# buttonsModule.net
KiCad netlist of a schematic drawn in EAGLE
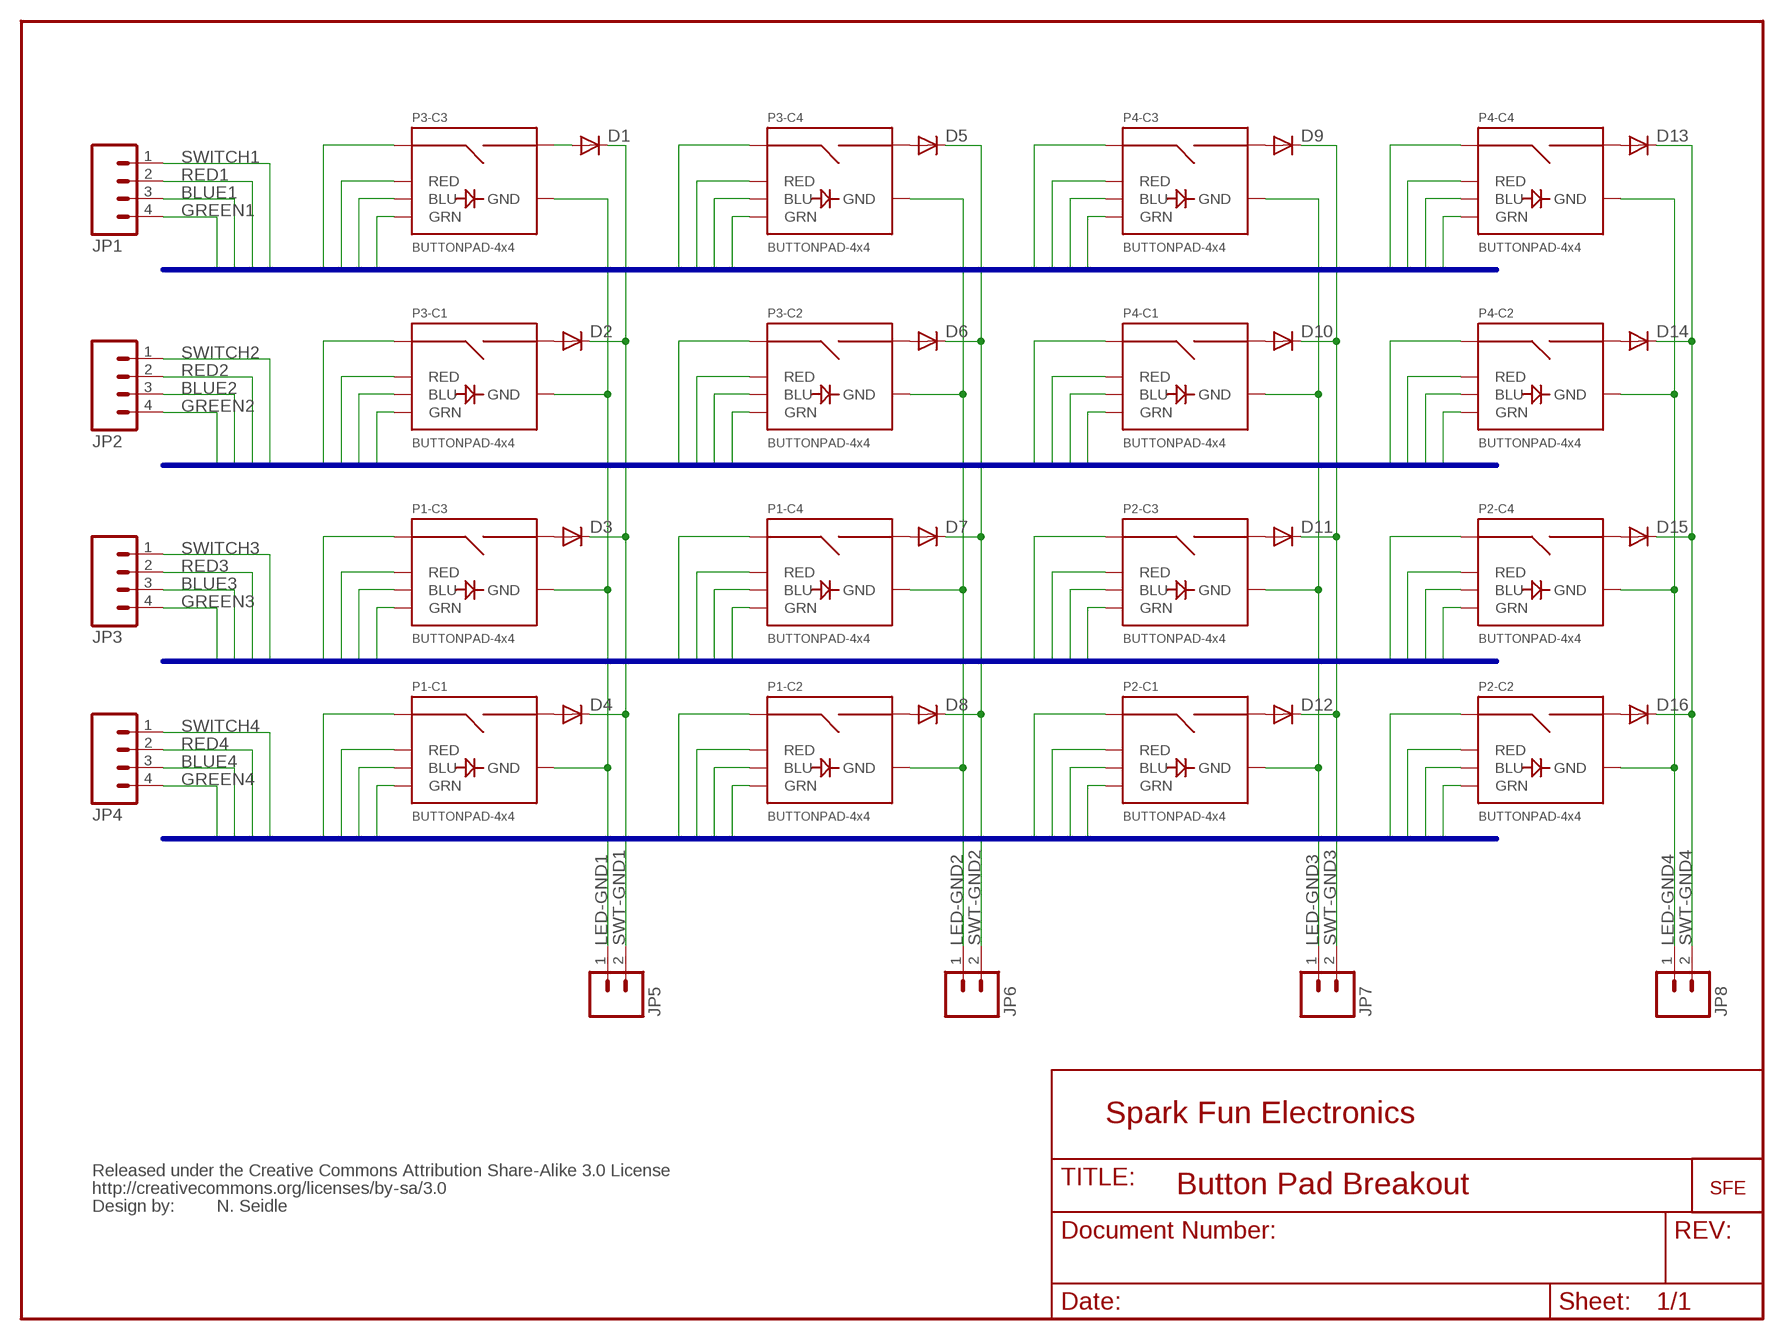
[diagram p0: schematic, sheet 1]

(export (version "E")
  (design (tool "Eeschema 10.0.6"))
  (components
    (comp (ref "D1")
      (value "DIODE-1N4148")
      (footprint "eagle-import:DOIDE-1N4148")
      (libsource (lib "eagle-import") (part "DIODE-1N4148"))
    )
    (comp (ref "D2")
      (value "DIODE-1N4148")
      (footprint "eagle-import:DOIDE-1N4148")
      (libsource (lib "eagle-import") (part "DIODE-1N4148"))
    )
    (comp (ref "D3")
      (value "DIODE-1N4148")
      (footprint "eagle-import:DOIDE-1N4148")
      (libsource (lib "eagle-import") (part "DIODE-1N4148"))
    )
    (comp (ref "D4")
      (value "DIODE-1N4148")
      (footprint "eagle-import:DOIDE-1N4148")
      (libsource (lib "eagle-import") (part "DIODE-1N4148"))
    )
    (comp (ref "D5")
      (value "DIODE-1N4148")
      (footprint "eagle-import:DOIDE-1N4148")
      (libsource (lib "eagle-import") (part "DIODE-1N4148"))
    )
    (comp (ref "D6")
      (value "DIODE-1N4148")
      (footprint "eagle-import:DOIDE-1N4148")
      (libsource (lib "eagle-import") (part "DIODE-1N4148"))
    )
    (comp (ref "D7")
      (value "DIODE-1N4148")
      (footprint "eagle-import:DOIDE-1N4148")
      (libsource (lib "eagle-import") (part "DIODE-1N4148"))
    )
    (comp (ref "D8")
      (value "DIODE-1N4148")
      (footprint "eagle-import:DOIDE-1N4148")
      (libsource (lib "eagle-import") (part "DIODE-1N4148"))
    )
    (comp (ref "D9")
      (value "DIODE-1N4148")
      (footprint "eagle-import:DOIDE-1N4148")
      (libsource (lib "eagle-import") (part "DIODE-1N4148"))
    )
    (comp (ref "D10")
      (value "DIODE-1N4148")
      (footprint "eagle-import:DOIDE-1N4148")
      (libsource (lib "eagle-import") (part "DIODE-1N4148"))
    )
    (comp (ref "D11")
      (value "DIODE-1N4148")
      (footprint "eagle-import:DOIDE-1N4148")
      (libsource (lib "eagle-import") (part "DIODE-1N4148"))
    )
    (comp (ref "D12")
      (value "DIODE-1N4148")
      (footprint "eagle-import:DOIDE-1N4148")
      (libsource (lib "eagle-import") (part "DIODE-1N4148"))
    )
    (comp (ref "D13")
      (value "DIODE-1N4148")
      (footprint "eagle-import:DOIDE-1N4148")
      (libsource (lib "eagle-import") (part "DIODE-1N4148"))
    )
    (comp (ref "D14")
      (value "DIODE-1N4148")
      (footprint "eagle-import:DOIDE-1N4148")
      (libsource (lib "eagle-import") (part "DIODE-1N4148"))
    )
    (comp (ref "D15")
      (value "DIODE-1N4148")
      (footprint "eagle-import:DOIDE-1N4148")
      (libsource (lib "eagle-import") (part "DIODE-1N4148"))
    )
    (comp (ref "D16")
      (value "DIODE-1N4148")
      (footprint "eagle-import:DOIDE-1N4148")
      (libsource (lib "eagle-import") (part "DIODE-1N4148"))
    )
    (comp (ref "JP1")
      (value "M04POLAR")
      (footprint "eagle-import:MOLEX-1X4")
      (libsource (lib "eagle-import") (part "M04POLAR"))
    )
    (comp (ref "JP2")
      (value "M04POLAR")
      (footprint "eagle-import:MOLEX-1X4")
      (libsource (lib "eagle-import") (part "M04POLAR"))
    )
    (comp (ref "JP3")
      (value "M04POLAR")
      (footprint "eagle-import:MOLEX-1X4")
      (libsource (lib "eagle-import") (part "M04POLAR"))
    )
    (comp (ref "JP4")
      (value "M04POLAR")
      (footprint "eagle-import:MOLEX-1X4")
      (libsource (lib "eagle-import") (part "M04POLAR"))
    )
    (comp (ref "JP5")
      (value "M02POLAR")
      (footprint "eagle-import:MOLEX-1X2")
      (libsource (lib "eagle-import") (part "M02POLAR"))
    )
    (comp (ref "JP6")
      (value "M02POLAR")
      (footprint "eagle-import:MOLEX-1X2")
      (libsource (lib "eagle-import") (part "M02POLAR"))
    )
    (comp (ref "JP7")
      (value "M02POLAR")
      (footprint "eagle-import:MOLEX-1X2")
      (libsource (lib "eagle-import") (part "M02POLAR"))
    )
    (comp (ref "JP8")
      (value "M02POLAR")
      (footprint "eagle-import:MOLEX-1X2")
      (libsource (lib "eagle-import") (part "M02POLAR"))
    )
    (comp (ref "P1")
      (value "BUTTONPAD-4x4")
      (footprint "eagle-import:BUTTONPAD-2X2")
      (libsource (lib "eagle-import") (part "BUTTONPAD-2X2"))
    )
    (comp (ref "P2")
      (value "BUTTONPAD-4x4")
      (footprint "eagle-import:BUTTONPAD-2X2")
      (libsource (lib "eagle-import") (part "BUTTONPAD-2X2"))
    )
    (comp (ref "P3")
      (value "BUTTONPAD-4x4")
      (footprint "eagle-import:BUTTONPAD-2X2")
      (libsource (lib "eagle-import") (part "BUTTONPAD-2X2"))
    )
    (comp (ref "P4")
      (value "BUTTONPAD-4x4")
      (footprint "eagle-import:BUTTONPAD-2X2")
      (libsource (lib "eagle-import") (part "BUTTONPAD-2X2"))
    )
    (comp (ref "U$1")
      (value "LOGO-SFE")
      (footprint "eagle-import:SFE-NEW-WEBLOGO")
      (libsource (lib "eagle-import") (part "LOGO-SFE"))
    )
    (comp (ref "U$2")
      (value "CREATIVE_COMMONS")
      (footprint "eagle-import:CREATIVE_COMMONS")
      (libsource (lib "eagle-import") (part "CREATIVE_COMMONS"))
    )
  )
  (nets
    (net (code "1") (name "/BLUE1") (class "Default")
      (node (ref "JP1") (pin "3") (pinfunction "3_3") (pintype "passive"))
      (node (ref "P3") (pin "BLU3") (pinfunction "BLU_BLU3") (pintype "bidirectional"))
      (node (ref "P3") (pin "BLU4") (pinfunction "BLU_BLU4") (pintype "bidirectional"))
      (node (ref "P4") (pin "BLU3") (pinfunction "BLU_BLU3") (pintype "bidirectional"))
      (node (ref "P4") (pin "BLU4") (pinfunction "BLU_BLU4") (pintype "bidirectional"))
    )
    (net (code "2") (name "/BLUE2") (class "Default")
      (node (ref "JP2") (pin "3") (pinfunction "3_3") (pintype "passive"))
      (node (ref "P3") (pin "BLU1") (pinfunction "BLU_BLU1") (pintype "bidirectional"))
      (node (ref "P3") (pin "BLU2") (pinfunction "BLU_BLU2") (pintype "bidirectional"))
      (node (ref "P4") (pin "BLU1") (pinfunction "BLU_BLU1") (pintype "bidirectional"))
      (node (ref "P4") (pin "BLU2") (pinfunction "BLU_BLU2") (pintype "bidirectional"))
    )
    (net (code "3") (name "/BLUE3") (class "Default")
      (node (ref "JP3") (pin "3") (pinfunction "3_3") (pintype "passive"))
      (node (ref "P1") (pin "BLU3") (pinfunction "BLU_BLU3") (pintype "bidirectional"))
      (node (ref "P1") (pin "BLU4") (pinfunction "BLU_BLU4") (pintype "bidirectional"))
      (node (ref "P2") (pin "BLU3") (pinfunction "BLU_BLU3") (pintype "bidirectional"))
      (node (ref "P2") (pin "BLU4") (pinfunction "BLU_BLU4") (pintype "bidirectional"))
    )
    (net (code "4") (name "/BLUE4") (class "Default")
      (node (ref "JP4") (pin "3") (pinfunction "3_3") (pintype "passive"))
      (node (ref "P1") (pin "BLU1") (pinfunction "BLU_BLU1") (pintype "bidirectional"))
      (node (ref "P1") (pin "BLU2") (pinfunction "BLU_BLU2") (pintype "bidirectional"))
      (node (ref "P2") (pin "BLU1") (pinfunction "BLU_BLU1") (pintype "bidirectional"))
      (node (ref "P2") (pin "BLU2") (pinfunction "BLU_BLU2") (pintype "bidirectional"))
    )
    (net (code "5") (name "/GREEN1") (class "Default")
      (node (ref "JP1") (pin "4") (pinfunction "4_4") (pintype "passive"))
      (node (ref "P3") (pin "GRN3") (pinfunction "GRN_GRN3") (pintype "bidirectional"))
      (node (ref "P3") (pin "GRN4") (pinfunction "GRN_GRN4") (pintype "bidirectional"))
      (node (ref "P4") (pin "GRN3") (pinfunction "GRN_GRN3") (pintype "bidirectional"))
      (node (ref "P4") (pin "GRN4") (pinfunction "GRN_GRN4") (pintype "bidirectional"))
    )
    (net (code "6") (name "/GREEN2") (class "Default")
      (node (ref "JP2") (pin "4") (pinfunction "4_4") (pintype "passive"))
      (node (ref "P3") (pin "GRN1") (pinfunction "GRN_GRN1") (pintype "bidirectional"))
      (node (ref "P3") (pin "GRN2") (pinfunction "GRN_GRN2") (pintype "bidirectional"))
      (node (ref "P4") (pin "GRN1") (pinfunction "GRN_GRN1") (pintype "bidirectional"))
      (node (ref "P4") (pin "GRN2") (pinfunction "GRN_GRN2") (pintype "bidirectional"))
    )
    (net (code "7") (name "/GREEN3") (class "Default")
      (node (ref "JP3") (pin "4") (pinfunction "4_4") (pintype "passive"))
      (node (ref "P1") (pin "GRN3") (pinfunction "GRN_GRN3") (pintype "bidirectional"))
      (node (ref "P1") (pin "GRN4") (pinfunction "GRN_GRN4") (pintype "bidirectional"))
      (node (ref "P2") (pin "GRN3") (pinfunction "GRN_GRN3") (pintype "bidirectional"))
      (node (ref "P2") (pin "GRN4") (pinfunction "GRN_GRN4") (pintype "bidirectional"))
    )
    (net (code "8") (name "/GREEN4") (class "Default")
      (node (ref "JP4") (pin "4") (pinfunction "4_4") (pintype "passive"))
      (node (ref "P1") (pin "GRN1") (pinfunction "GRN_GRN1") (pintype "bidirectional"))
      (node (ref "P1") (pin "GRN2") (pinfunction "GRN_GRN2") (pintype "bidirectional"))
      (node (ref "P2") (pin "GRN1") (pinfunction "GRN_GRN1") (pintype "bidirectional"))
      (node (ref "P2") (pin "GRN2") (pinfunction "GRN_GRN2") (pintype "bidirectional"))
    )
    (net (code "9") (name "/LED-GND1") (class "Default")
      (node (ref "JP5") (pin "1") (pinfunction "1_1") (pintype "passive"))
      (node (ref "P1") (pin "GND1") (pinfunction "GND_GND1") (pintype "bidirectional"))
      (node (ref "P1") (pin "GND3") (pinfunction "GND_GND3") (pintype "bidirectional"))
      (node (ref "P3") (pin "GND1") (pinfunction "GND_GND1") (pintype "bidirectional"))
      (node (ref "P3") (pin "GND3") (pinfunction "GND_GND3") (pintype "bidirectional"))
    )
    (net (code "10") (name "/LED-GND2") (class "Default")
      (node (ref "JP6") (pin "1") (pinfunction "1_1") (pintype "passive"))
      (node (ref "P1") (pin "GND2") (pinfunction "GND_GND2") (pintype "bidirectional"))
      (node (ref "P1") (pin "GND4") (pinfunction "GND_GND4") (pintype "bidirectional"))
      (node (ref "P3") (pin "GND2") (pinfunction "GND_GND2") (pintype "bidirectional"))
      (node (ref "P3") (pin "GND4") (pinfunction "GND_GND4") (pintype "bidirectional"))
    )
    (net (code "11") (name "/LED-GND3") (class "Default")
      (node (ref "JP7") (pin "1") (pinfunction "1_1") (pintype "passive"))
      (node (ref "P2") (pin "GND1") (pinfunction "GND_GND1") (pintype "bidirectional"))
      (node (ref "P2") (pin "GND3") (pinfunction "GND_GND3") (pintype "bidirectional"))
      (node (ref "P4") (pin "GND1") (pinfunction "GND_GND1") (pintype "bidirectional"))
      (node (ref "P4") (pin "GND3") (pinfunction "GND_GND3") (pintype "bidirectional"))
    )
    (net (code "12") (name "/LED-GND4") (class "Default")
      (node (ref "JP8") (pin "1") (pinfunction "1_1") (pintype "passive"))
      (node (ref "P2") (pin "GND2") (pinfunction "GND_GND2") (pintype "bidirectional"))
      (node (ref "P2") (pin "GND4") (pinfunction "GND_GND4") (pintype "bidirectional"))
      (node (ref "P4") (pin "GND2") (pinfunction "GND_GND2") (pintype "bidirectional"))
      (node (ref "P4") (pin "GND4") (pinfunction "GND_GND4") (pintype "bidirectional"))
    )
    (net (code "13") (name "/RED1") (class "Default")
      (node (ref "JP1") (pin "2") (pinfunction "2_2") (pintype "passive"))
      (node (ref "P3") (pin "RED3") (pinfunction "RED_RED3") (pintype "bidirectional"))
      (node (ref "P3") (pin "RED4") (pinfunction "RED_RED4") (pintype "bidirectional"))
      (node (ref "P4") (pin "RED3") (pinfunction "RED_RED3") (pintype "bidirectional"))
      (node (ref "P4") (pin "RED4") (pinfunction "RED_RED4") (pintype "bidirectional"))
    )
    (net (code "14") (name "/RED2") (class "Default")
      (node (ref "JP2") (pin "2") (pinfunction "2_2") (pintype "passive"))
      (node (ref "P3") (pin "RED1") (pinfunction "RED_RED1") (pintype "bidirectional"))
      (node (ref "P3") (pin "RED2") (pinfunction "RED_RED2") (pintype "bidirectional"))
      (node (ref "P4") (pin "RED1") (pinfunction "RED_RED1") (pintype "bidirectional"))
      (node (ref "P4") (pin "RED2") (pinfunction "RED_RED2") (pintype "bidirectional"))
    )
    (net (code "15") (name "/RED3") (class "Default")
      (node (ref "JP3") (pin "2") (pinfunction "2_2") (pintype "passive"))
      (node (ref "P1") (pin "RED3") (pinfunction "RED_RED3") (pintype "bidirectional"))
      (node (ref "P1") (pin "RED4") (pinfunction "RED_RED4") (pintype "bidirectional"))
      (node (ref "P2") (pin "RED3") (pinfunction "RED_RED3") (pintype "bidirectional"))
      (node (ref "P2") (pin "RED4") (pinfunction "RED_RED4") (pintype "bidirectional"))
    )
    (net (code "16") (name "/RED4") (class "Default")
      (node (ref "JP4") (pin "2") (pinfunction "2_2") (pintype "passive"))
      (node (ref "P1") (pin "RED1") (pinfunction "RED_RED1") (pintype "bidirectional"))
      (node (ref "P1") (pin "RED2") (pinfunction "RED_RED2") (pintype "bidirectional"))
      (node (ref "P2") (pin "RED1") (pinfunction "RED_RED1") (pintype "bidirectional"))
      (node (ref "P2") (pin "RED2") (pinfunction "RED_RED2") (pintype "bidirectional"))
    )
    (net (code "17") (name "/SWITCH1") (class "Default")
      (node (ref "JP1") (pin "1") (pinfunction "1_1") (pintype "passive"))
      (node (ref "P3") (pin "SIG5") (pinfunction "SIG1_SIG5") (pintype "bidirectional"))
      (node (ref "P3") (pin "SIG7") (pinfunction "SIG1_SIG7") (pintype "bidirectional"))
      (node (ref "P4") (pin "SIG5") (pinfunction "SIG1_SIG5") (pintype "bidirectional"))
      (node (ref "P4") (pin "SIG7") (pinfunction "SIG1_SIG7") (pintype "bidirectional"))
    )
    (net (code "18") (name "/SWITCH2") (class "Default")
      (node (ref "JP2") (pin "1") (pinfunction "1_1") (pintype "passive"))
      (node (ref "P3") (pin "SIG1") (pinfunction "SIG1_SIG1") (pintype "bidirectional"))
      (node (ref "P3") (pin "SIG3") (pinfunction "SIG1_SIG3") (pintype "bidirectional"))
      (node (ref "P4") (pin "SIG1") (pinfunction "SIG1_SIG1") (pintype "bidirectional"))
      (node (ref "P4") (pin "SIG3") (pinfunction "SIG1_SIG3") (pintype "bidirectional"))
    )
    (net (code "19") (name "/SWITCH3") (class "Default")
      (node (ref "JP3") (pin "1") (pinfunction "1_1") (pintype "passive"))
      (node (ref "P1") (pin "SIG5") (pinfunction "SIG1_SIG5") (pintype "bidirectional"))
      (node (ref "P1") (pin "SIG7") (pinfunction "SIG1_SIG7") (pintype "bidirectional"))
      (node (ref "P2") (pin "SIG5") (pinfunction "SIG1_SIG5") (pintype "bidirectional"))
      (node (ref "P2") (pin "SIG7") (pinfunction "SIG1_SIG7") (pintype "bidirectional"))
    )
    (net (code "20") (name "/SWITCH4") (class "Default")
      (node (ref "JP4") (pin "1") (pinfunction "1_1") (pintype "passive"))
      (node (ref "P1") (pin "SIG1") (pinfunction "SIG1_SIG1") (pintype "bidirectional"))
      (node (ref "P1") (pin "SIG3") (pinfunction "SIG1_SIG3") (pintype "bidirectional"))
      (node (ref "P2") (pin "SIG1") (pinfunction "SIG1_SIG1") (pintype "bidirectional"))
      (node (ref "P2") (pin "SIG3") (pinfunction "SIG1_SIG3") (pintype "bidirectional"))
    )
    (net (code "21") (name "/SWT-GND1") (class "Default")
      (node (ref "D1") (pin "P$2") (pinfunction "C_P$2") (pintype "passive"))
      (node (ref "D2") (pin "P$2") (pinfunction "C_P$2") (pintype "passive"))
      (node (ref "D3") (pin "P$2") (pinfunction "C_P$2") (pintype "passive"))
      (node (ref "D4") (pin "P$2") (pinfunction "C_P$2") (pintype "passive"))
      (node (ref "JP5") (pin "2") (pinfunction "2_2") (pintype "passive"))
    )
    (net (code "22") (name "/SWT-GND2") (class "Default")
      (node (ref "D5") (pin "P$2") (pinfunction "C_P$2") (pintype "passive"))
      (node (ref "D6") (pin "P$2") (pinfunction "C_P$2") (pintype "passive"))
      (node (ref "D7") (pin "P$2") (pinfunction "C_P$2") (pintype "passive"))
      (node (ref "D8") (pin "P$2") (pinfunction "C_P$2") (pintype "passive"))
      (node (ref "JP6") (pin "2") (pinfunction "2_2") (pintype "passive"))
    )
    (net (code "23") (name "/SWT-GND3") (class "Default")
      (node (ref "D10") (pin "P$2") (pinfunction "C_P$2") (pintype "passive"))
      (node (ref "D11") (pin "P$2") (pinfunction "C_P$2") (pintype "passive"))
      (node (ref "D12") (pin "P$2") (pinfunction "C_P$2") (pintype "passive"))
      (node (ref "D9") (pin "P$2") (pinfunction "C_P$2") (pintype "passive"))
      (node (ref "JP7") (pin "2") (pinfunction "2_2") (pintype "passive"))
    )
    (net (code "24") (name "/SWT-GND4") (class "Default")
      (node (ref "D13") (pin "P$2") (pinfunction "C_P$2") (pintype "passive"))
      (node (ref "D14") (pin "P$2") (pinfunction "C_P$2") (pintype "passive"))
      (node (ref "D15") (pin "P$2") (pinfunction "C_P$2") (pintype "passive"))
      (node (ref "D16") (pin "P$2") (pinfunction "C_P$2") (pintype "passive"))
      (node (ref "JP8") (pin "2") (pinfunction "2_2") (pintype "passive"))
    )
    (net (code "25") (name "Net-(D1-A)") (class "Default")
      (node (ref "D1") (pin "P$1") (pinfunction "A_P$1") (pintype "passive"))
      (node (ref "P3") (pin "SIG6") (pinfunction "SIG2_SIG6") (pintype "bidirectional"))
    )
    (net (code "26") (name "Net-(D2-A)") (class "Default")
      (node (ref "D2") (pin "P$1") (pinfunction "A_P$1") (pintype "passive"))
      (node (ref "P3") (pin "SIG2") (pinfunction "SIG2_SIG2") (pintype "bidirectional"))
    )
    (net (code "27") (name "Net-(D3-A)") (class "Default")
      (node (ref "D3") (pin "P$1") (pinfunction "A_P$1") (pintype "passive"))
      (node (ref "P1") (pin "SIG6") (pinfunction "SIG2_SIG6") (pintype "bidirectional"))
    )
    (net (code "28") (name "Net-(D4-A)") (class "Default")
      (node (ref "D4") (pin "P$1") (pinfunction "A_P$1") (pintype "passive"))
      (node (ref "P1") (pin "SIG2") (pinfunction "SIG2_SIG2") (pintype "bidirectional"))
    )
    (net (code "29") (name "Net-(D5-A)") (class "Default")
      (node (ref "D5") (pin "P$1") (pinfunction "A_P$1") (pintype "passive"))
      (node (ref "P3") (pin "SIG8") (pinfunction "SIG2_SIG8") (pintype "bidirectional"))
    )
    (net (code "30") (name "Net-(D6-A)") (class "Default")
      (node (ref "D6") (pin "P$1") (pinfunction "A_P$1") (pintype "passive"))
      (node (ref "P3") (pin "SIG4") (pinfunction "SIG2_SIG4") (pintype "bidirectional"))
    )
    (net (code "31") (name "Net-(D7-A)") (class "Default")
      (node (ref "D7") (pin "P$1") (pinfunction "A_P$1") (pintype "passive"))
      (node (ref "P1") (pin "SIG8") (pinfunction "SIG2_SIG8") (pintype "bidirectional"))
    )
    (net (code "32") (name "Net-(D8-A)") (class "Default")
      (node (ref "D8") (pin "P$1") (pinfunction "A_P$1") (pintype "passive"))
      (node (ref "P1") (pin "SIG4") (pinfunction "SIG2_SIG4") (pintype "bidirectional"))
    )
    (net (code "33") (name "Net-(D9-A)") (class "Default")
      (node (ref "D9") (pin "P$1") (pinfunction "A_P$1") (pintype "passive"))
      (node (ref "P4") (pin "SIG6") (pinfunction "SIG2_SIG6") (pintype "bidirectional"))
    )
    (net (code "34") (name "Net-(D10-A)") (class "Default")
      (node (ref "D10") (pin "P$1") (pinfunction "A_P$1") (pintype "passive"))
      (node (ref "P4") (pin "SIG2") (pinfunction "SIG2_SIG2") (pintype "bidirectional"))
    )
    (net (code "35") (name "Net-(D11-A)") (class "Default")
      (node (ref "D11") (pin "P$1") (pinfunction "A_P$1") (pintype "passive"))
      (node (ref "P2") (pin "SIG6") (pinfunction "SIG2_SIG6") (pintype "bidirectional"))
    )
    (net (code "36") (name "Net-(D12-A)") (class "Default")
      (node (ref "D12") (pin "P$1") (pinfunction "A_P$1") (pintype "passive"))
      (node (ref "P2") (pin "SIG2") (pinfunction "SIG2_SIG2") (pintype "bidirectional"))
    )
    (net (code "37") (name "Net-(D13-A)") (class "Default")
      (node (ref "D13") (pin "P$1") (pinfunction "A_P$1") (pintype "passive"))
      (node (ref "P4") (pin "SIG8") (pinfunction "SIG2_SIG8") (pintype "bidirectional"))
    )
    (net (code "38") (name "Net-(D14-A)") (class "Default")
      (node (ref "D14") (pin "P$1") (pinfunction "A_P$1") (pintype "passive"))
      (node (ref "P4") (pin "SIG4") (pinfunction "SIG2_SIG4") (pintype "bidirectional"))
    )
    (net (code "39") (name "Net-(D15-A)") (class "Default")
      (node (ref "D15") (pin "P$1") (pinfunction "A_P$1") (pintype "passive"))
      (node (ref "P2") (pin "SIG8") (pinfunction "SIG2_SIG8") (pintype "bidirectional"))
    )
    (net (code "40") (name "Net-(D16-A)") (class "Default")
      (node (ref "D16") (pin "P$1") (pinfunction "A_P$1") (pintype "passive"))
      (node (ref "P2") (pin "SIG4") (pinfunction "SIG2_SIG4") (pintype "bidirectional"))
    )
  )
)
